# Lidar_Robot_Power.net
KiCad netlist of a schematic drawn in Altium Designer
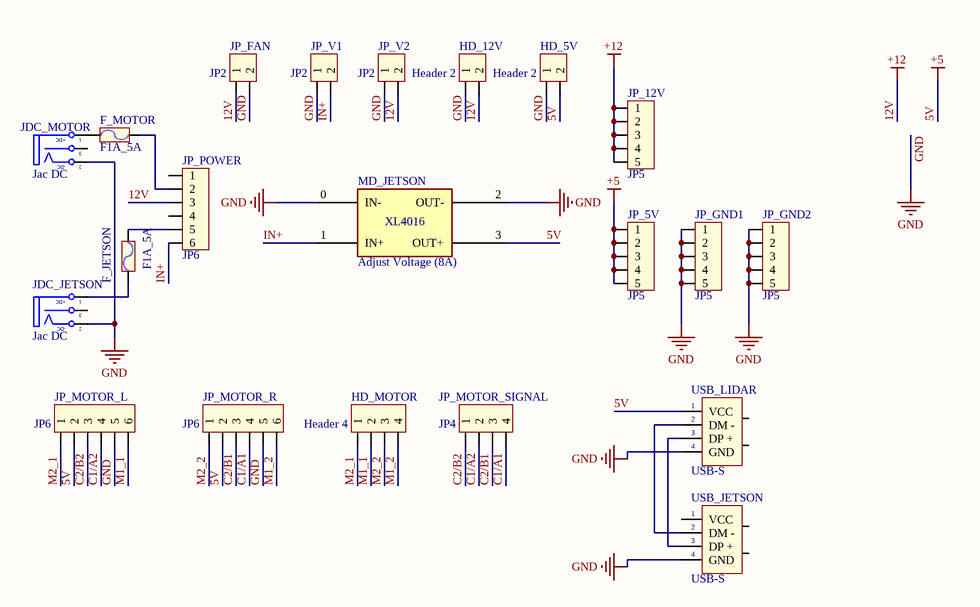
[diagram p0: Lidar_Robot_Power.SchDoc]

(export (version "E")
  (design (tool "Eeschema 10.0.6"))
  (components
    (comp (ref "F_JETSON")
      (value "F1A_5A")
      (footprint "FUSE2")
      (description "Fuse")
      (fields (field (name "DESIGNED BY") "VanDungEvn"))
      (libsource (lib "syhaunguyen") (part "Fuse"))
    )
    (comp (ref "F_MOTOR")
      (value "F1A_5A")
      (footprint "FUSE2")
      (description "Fuse")
      (fields (field (name "DESIGNED BY") "VanDungEvn"))
      (libsource (lib "") (part "Fuse_1"))
    )
    (comp (ref "HD_5V")
      (value "Header 2")
      (footprint "HED2")
      (description "Header 2 (Green)")
      (libsource (lib "syhaunguyen") (part "Hed2"))
    )
    (comp (ref "HD_12V")
      (value "Header 2")
      (footprint "HED2")
      (description "Header 2 (Green)")
      (libsource (lib "syhaunguyen") (part "Hed2"))
    )
    (comp (ref "HD_MOTOR")
      (value "Header 4")
      (footprint "HED4")
      (description "Header 4 (Green)")
      (libsource (lib "syhaunguyen") (part "Hed4"))
    )
    (comp (ref "JDC_JETSON")
      (value "Jac DC")
      (footprint "DC-IN")
      (description "Jac DC input")
      (libsource (lib "syhaunguyen") (part "DCIN"))
    )
    (comp (ref "JDC_MOTOR")
      (value "Jac DC")
      (footprint "DC-IN")
      (description "Jac DC input")
      (libsource (lib "syhaunguyen") (part "DCIN"))
    )
    (comp (ref "JP_5V")
      (value "JP5")
      (footprint "CON5")
      (description "Connector 5")
      (libsource (lib "syhaunguyen") (part "Con5"))
    )
    (comp (ref "JP_12V")
      (value "JP5")
      (footprint "CON5")
      (description "Connector 5")
      (libsource (lib "syhaunguyen") (part "Con5"))
    )
    (comp (ref "JP_FAN")
      (value "JP2")
      (footprint "CON2")
      (description "Connector 2")
      (libsource (lib "syhaunguyen") (part "Con2"))
    )
    (comp (ref "JP_GND1")
      (value "JP5")
      (footprint "CON5")
      (description "Connector 5")
      (libsource (lib "syhaunguyen") (part "Con5"))
    )
    (comp (ref "JP_GND2")
      (value "JP5")
      (footprint "CON5")
      (description "Connector 5")
      (libsource (lib "syhaunguyen") (part "Con5"))
    )
    (comp (ref "JP_MOTOR_L")
      (value "JP6")
      (footprint "CON6")
      (description "Connector 6")
      (libsource (lib "syhaunguyen") (part "Con6"))
    )
    (comp (ref "JP_MOTOR_R")
      (value "JP6")
      (footprint "CON6")
      (description "Connector 6")
      (libsource (lib "syhaunguyen") (part "Con6"))
    )
    (comp (ref "JP_MOTOR_SIGNAL")
      (value "JP4")
      (footprint "CON4")
      (description "Connector 4")
      (libsource (lib "syhaunguyen") (part "Con4"))
    )
    (comp (ref "JP_POWER")
      (value "JP6")
      (footprint "CON6")
      (description "Connector 6")
      (libsource (lib "") (part "Con6_1"))
    )
    (comp (ref "JP_V1")
      (value "JP2")
      (footprint "CON2")
      (description "Connector 2")
      (libsource (lib "syhaunguyen") (part "Con2"))
    )
    (comp (ref "JP_V2")
      (value "JP2")
      (footprint "CON2")
      (description "Connector 2")
      (libsource (lib "syhaunguyen") (part "Con2"))
    )
    (comp (ref "MD_JETSON")
      (value "Adjust Voltage (8A)")
      (footprint "XL4016")
      (libsource (lib "Mylib") (part "XL4016"))
    )
    (comp (ref "USB_JETSON")
      (value "USB-S")
      (footprint "USB-A")
      (description "USB connector")
      (libsource (lib "syhaunguyen") (part "USB_S"))
    )
    (comp (ref "USB_LIDAR")
      (value "USB-S")
      (footprint "USB-A")
      (description "USB connector")
      (libsource (lib "syhaunguyen") (part "USB_S"))
    )
  )
  (nets
    (net (code "1") (name "+5") (class "Default")
      (node (ref "HD_5V") (pin "2") (pinfunction "2_2") (pintype "passive"))
      (node (ref "JP_5V") (pin "1") (pinfunction "1_1") (pintype "passive"))
      (node (ref "JP_5V") (pin "2") (pinfunction "2_2") (pintype "passive"))
      (node (ref "JP_5V") (pin "3") (pinfunction "3_3") (pintype "passive"))
      (node (ref "JP_5V") (pin "4") (pinfunction "4_4") (pintype "passive"))
      (node (ref "JP_5V") (pin "5") (pinfunction "5_5") (pintype "passive"))
      (node (ref "JP_MOTOR_L") (pin "2") (pinfunction "2_2") (pintype "passive"))
      (node (ref "JP_MOTOR_R") (pin "2") (pinfunction "2_2") (pintype "passive"))
      (node (ref "MD_JETSON") (pin "3") (pinfunction "OUT+_3") (pintype "power_in"))
      (node (ref "USB_LIDAR") (pin "1") (pinfunction "VCC_1") (pintype "passive"))
    )
    (net (code "2") (name "+12") (class "Default")
      (node (ref "HD_12V") (pin "2") (pinfunction "2_2") (pintype "passive"))
      (node (ref "JP_12V") (pin "1") (pinfunction "1_1") (pintype "passive"))
      (node (ref "JP_12V") (pin "2") (pinfunction "2_2") (pintype "passive"))
      (node (ref "JP_12V") (pin "3") (pinfunction "3_3") (pintype "passive"))
      (node (ref "JP_12V") (pin "4") (pinfunction "4_4") (pintype "passive"))
      (node (ref "JP_12V") (pin "5") (pinfunction "5_5") (pintype "passive"))
      (node (ref "JP_FAN") (pin "1") (pinfunction "1_1") (pintype "passive"))
      (node (ref "JP_POWER") (pin "3") (pinfunction "3_3") (pintype "passive"))
      (node (ref "JP_V2") (pin "2") (pinfunction "2_2") (pintype "passive"))
    )
    (net (code "3") (name "/C1{slash}A1") (class "Default")
      (node (ref "JP_MOTOR_R") (pin "4") (pinfunction "4_4") (pintype "passive"))
      (node (ref "JP_MOTOR_SIGNAL") (pin "4") (pinfunction "4_4") (pintype "passive"))
    )
    (net (code "4") (name "/C1{slash}A2") (class "Default")
      (node (ref "JP_MOTOR_L") (pin "4") (pinfunction "4_4") (pintype "passive"))
      (node (ref "JP_MOTOR_SIGNAL") (pin "2") (pinfunction "2_2") (pintype "passive"))
    )
    (net (code "5") (name "/C2{slash}B1") (class "Default")
      (node (ref "JP_MOTOR_R") (pin "3") (pinfunction "3_3") (pintype "passive"))
      (node (ref "JP_MOTOR_SIGNAL") (pin "3") (pinfunction "3_3") (pintype "passive"))
    )
    (net (code "6") (name "/C2{slash}B2") (class "Default")
      (node (ref "JP_MOTOR_L") (pin "3") (pinfunction "3_3") (pintype "passive"))
      (node (ref "JP_MOTOR_SIGNAL") (pin "1") (pinfunction "1_1") (pintype "passive"))
    )
    (net (code "7") (name "/IN+") (class "Default")
      (node (ref "JP_POWER") (pin "6") (pinfunction "6_6") (pintype "passive"))
      (node (ref "JP_V1") (pin "2") (pinfunction "2_2") (pintype "passive"))
      (node (ref "MD_JETSON") (pin "1") (pinfunction "IN+_1") (pintype "power_in"))
    )
    (net (code "8") (name "/M1_1") (class "Default")
      (node (ref "HD_MOTOR") (pin "2") (pinfunction "2_2") (pintype "passive"))
      (node (ref "JP_MOTOR_L") (pin "6") (pinfunction "6_6") (pintype "passive"))
    )
    (net (code "9") (name "/M1_2") (class "Default")
      (node (ref "HD_MOTOR") (pin "4") (pinfunction "4_4") (pintype "passive"))
      (node (ref "JP_MOTOR_R") (pin "6") (pinfunction "6_6") (pintype "passive"))
    )
    (net (code "10") (name "/M2_1") (class "Default")
      (node (ref "HD_MOTOR") (pin "1") (pinfunction "1_1") (pintype "passive"))
      (node (ref "JP_MOTOR_L") (pin "1") (pinfunction "1_1") (pintype "passive"))
    )
    (net (code "11") (name "/M2_2") (class "Default")
      (node (ref "HD_MOTOR") (pin "3") (pinfunction "3_3") (pintype "passive"))
      (node (ref "JP_MOTOR_R") (pin "1") (pinfunction "1_1") (pintype "passive"))
    )
    (net (code "12") (name "GND") (class "Default")
      (node (ref "HD_12V") (pin "1") (pinfunction "1_1") (pintype "passive"))
      (node (ref "HD_5V") (pin "1") (pinfunction "1_1") (pintype "passive"))
      (node (ref "JDC_JETSON") (pin "2") (pinfunction "TN_2") (pintype "passive"))
      (node (ref "JDC_MOTOR") (pin "2") (pinfunction "TN_2") (pintype "passive"))
      (node (ref "JP_FAN") (pin "2") (pinfunction "2_2") (pintype "passive"))
      (node (ref "JP_GND1") (pin "1") (pinfunction "1_1") (pintype "passive"))
      (node (ref "JP_GND1") (pin "2") (pinfunction "2_2") (pintype "passive"))
      (node (ref "JP_GND1") (pin "3") (pinfunction "3_3") (pintype "passive"))
      (node (ref "JP_GND1") (pin "4") (pinfunction "4_4") (pintype "passive"))
      (node (ref "JP_GND1") (pin "5") (pinfunction "5_5") (pintype "passive"))
      (node (ref "JP_GND2") (pin "1") (pinfunction "1_1") (pintype "passive"))
      (node (ref "JP_GND2") (pin "2") (pinfunction "2_2") (pintype "passive"))
      (node (ref "JP_GND2") (pin "3") (pinfunction "3_3") (pintype "passive"))
      (node (ref "JP_GND2") (pin "4") (pinfunction "4_4") (pintype "passive"))
      (node (ref "JP_GND2") (pin "5") (pinfunction "5_5") (pintype "passive"))
      (node (ref "JP_MOTOR_L") (pin "5") (pinfunction "5_5") (pintype "passive"))
      (node (ref "JP_MOTOR_R") (pin "5") (pinfunction "5_5") (pintype "passive"))
      (node (ref "JP_V1") (pin "1") (pinfunction "1_1") (pintype "passive"))
      (node (ref "JP_V2") (pin "1") (pinfunction "1_1") (pintype "passive"))
      (node (ref "MD_JETSON") (pin "0") (pinfunction "IN-_0") (pintype "power_in"))
      (node (ref "MD_JETSON") (pin "2") (pinfunction "OUT-_2") (pintype "power_in"))
      (node (ref "USB_JETSON") (pin "4") (pinfunction "GND_4") (pintype "passive"))
      (node (ref "USB_LIDAR") (pin "4") (pinfunction "GND_4") (pintype "passive"))
    )
    (net (code "13") (name "Net-(F_JETSON-Pad2)") (class "Default")
      (node (ref "F_JETSON") (pin "2") (pinfunction "2_2") (pintype "passive"))
      (node (ref "JP_POWER") (pin "5") (pinfunction "5_5") (pintype "passive"))
    )
    (net (code "14") (name "Net-(F_MOTOR-Pad2)") (class "Default")
      (node (ref "F_MOTOR") (pin "2") (pinfunction "2_2") (pintype "passive"))
      (node (ref "JP_POWER") (pin "2") (pinfunction "2_2") (pintype "passive"))
    )
    (net (code "15") (name "Net-(JDC_JETSON-T)") (class "Default")
      (node (ref "F_JETSON") (pin "1") (pinfunction "1_1") (pintype "passive"))
      (node (ref "JDC_JETSON") (pin "1") (pinfunction "T_1") (pintype "passive"))
    )
    (net (code "16") (name "Net-(JDC_MOTOR-T)") (class "Default")
      (node (ref "F_MOTOR") (pin "1") (pinfunction "1_1") (pintype "passive"))
      (node (ref "JDC_MOTOR") (pin "1") (pinfunction "T_1") (pintype "passive"))
    )
    (net (code "17") (name "Net-(USB_JETSON-DM_-)") (class "Default")
      (node (ref "USB_JETSON") (pin "2") (pinfunction "DM_-_2") (pintype "passive"))
      (node (ref "USB_LIDAR") (pin "2") (pinfunction "DM_-_2") (pintype "passive"))
    )
    (net (code "18") (name "Net-(USB_JETSON-DP_+)") (class "Default")
      (node (ref "USB_JETSON") (pin "3") (pinfunction "DP_+_3") (pintype "passive"))
      (node (ref "USB_LIDAR") (pin "3") (pinfunction "DP_+_3") (pintype "passive"))
    )
    (net (code "19") (name "unconnected-(JDC_JETSON-S-Pad3)") (class "Default")
      (node (ref "JDC_JETSON") (pin "3") (pinfunction "S_3") (pintype "power_in"))
    )
    (net (code "20") (name "unconnected-(JDC_MOTOR-S-Pad3)") (class "Default")
      (node (ref "JDC_MOTOR") (pin "3") (pinfunction "S_3") (pintype "power_in"))
    )
    (net (code "21") (name "unconnected-(JP_POWER-Pad1)") (class "Default")
      (node (ref "JP_POWER") (pin "1") (pinfunction "1_1") (pintype "passive"))
    )
    (net (code "22") (name "unconnected-(JP_POWER-Pad4)") (class "Default")
      (node (ref "JP_POWER") (pin "4") (pinfunction "4_4") (pintype "passive"))
    )
    (net (code "23") (name "unconnected-(USB_JETSON-Pad5)") (class "Default")
      (node (ref "USB_JETSON") (pin "5") (pinfunction "5_5") (pintype "passive"))
    )
    (net (code "24") (name "unconnected-(USB_JETSON-Pad6)") (class "Default")
      (node (ref "USB_JETSON") (pin "6") (pinfunction "6_6") (pintype "passive"))
    )
    (net (code "25") (name "unconnected-(USB_JETSON-VCC-Pad1)") (class "Default")
      (node (ref "USB_JETSON") (pin "1") (pinfunction "VCC_1") (pintype "passive"))
    )
    (net (code "26") (name "unconnected-(USB_LIDAR-Pad5)") (class "Default")
      (node (ref "USB_LIDAR") (pin "5") (pinfunction "5_5") (pintype "passive"))
    )
    (net (code "27") (name "unconnected-(USB_LIDAR-Pad6)") (class "Default")
      (node (ref "USB_LIDAR") (pin "6") (pinfunction "6_6") (pintype "passive"))
    )
  )
)
